# Vario_Kobo_SIDE_V1.net
KiCad netlist of a schematic drawn in EAGLE
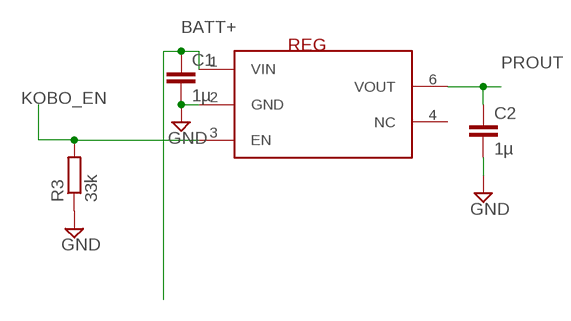
[diagram p0: schematic, sheet 1]
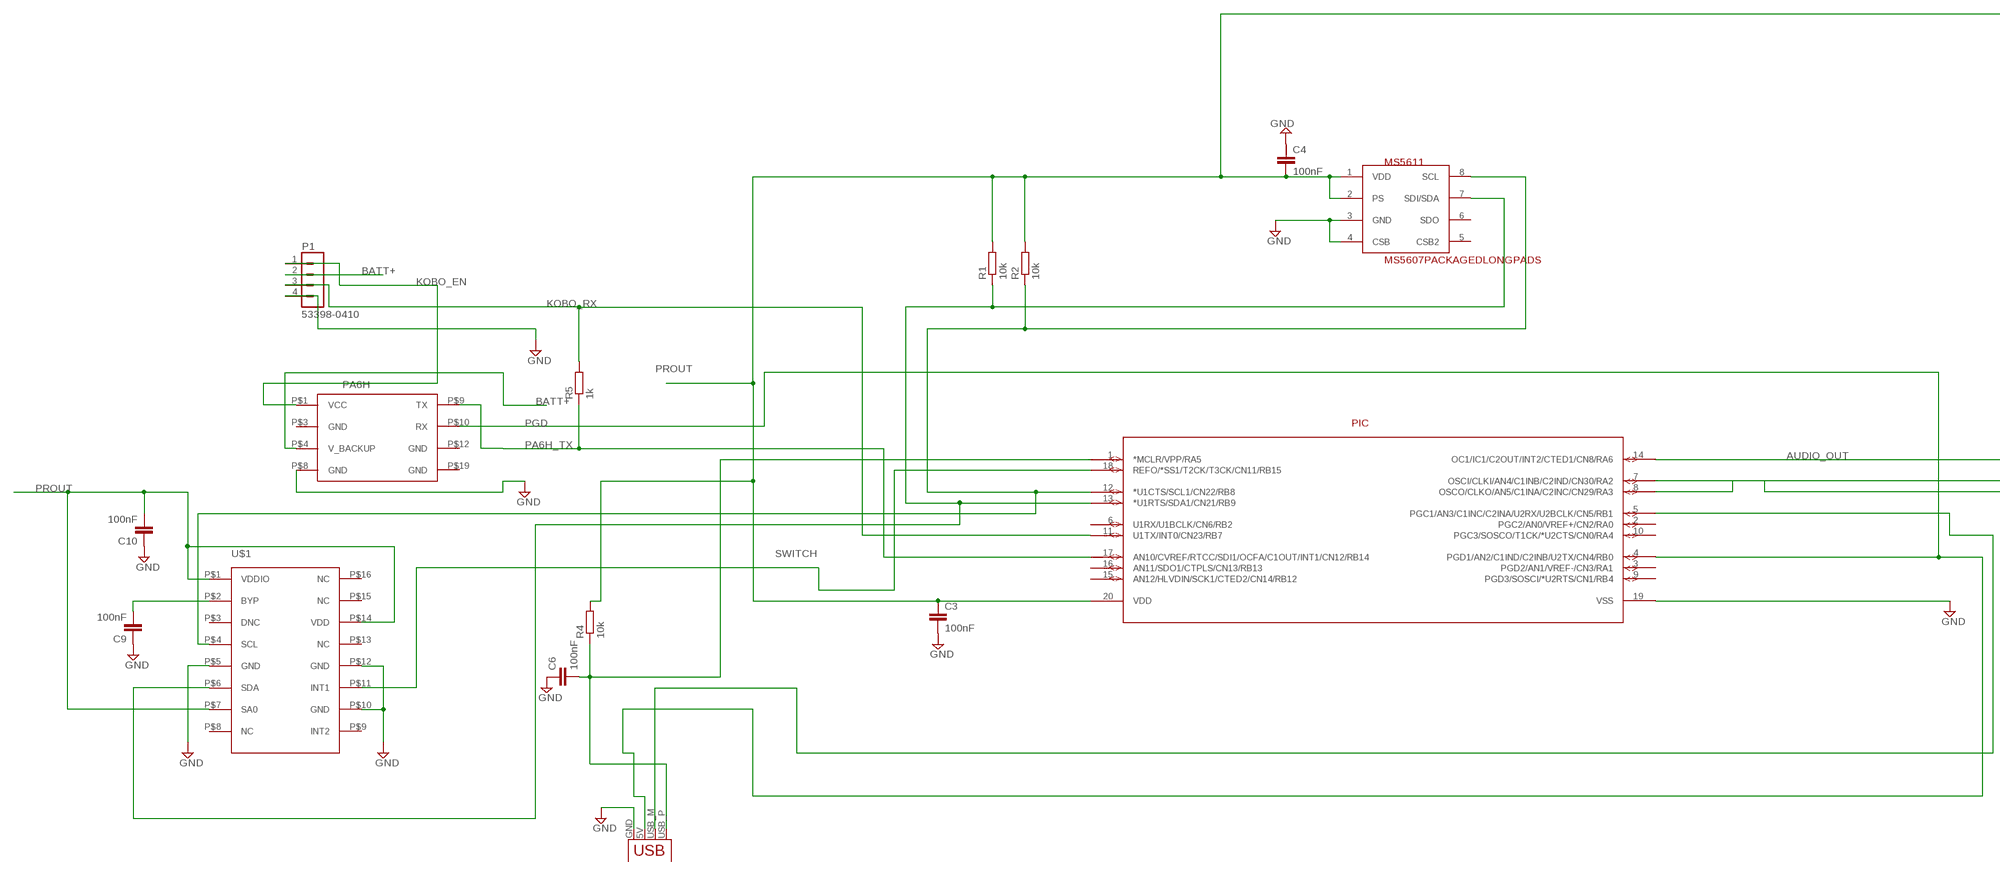
[diagram p1: schematic, sheet 2, part 1 of 2]
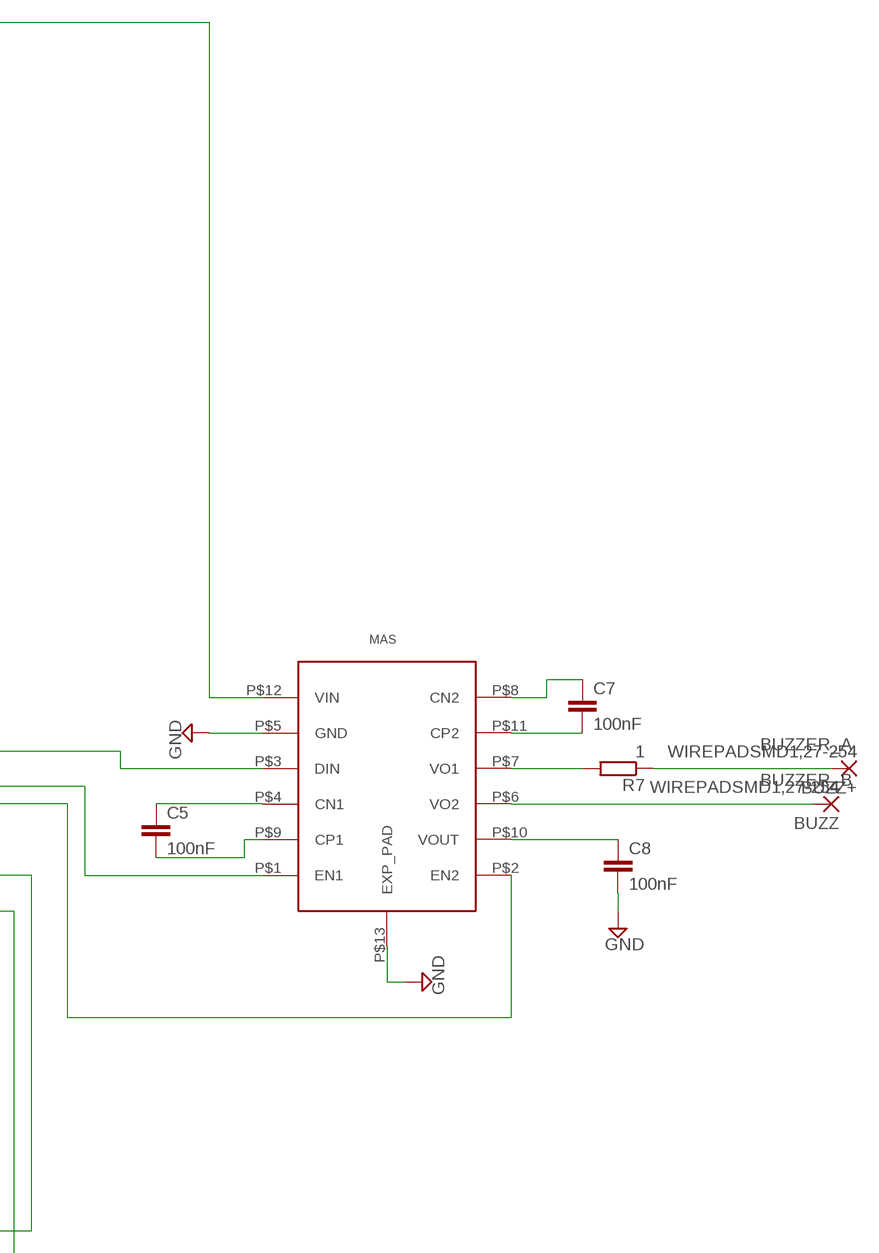
[diagram p2: schematic, sheet 2, part 2 of 2]

(export (version "E")
  (design (tool "Eeschema 10.0.6"))
  (components
    (comp (ref "BUZZ")
      (value "WIREPADSMD1,27-254")
      (footprint "eagle-import:SMD1,27-2,54")
      (libsource (lib "eagle-import") (part "WIREPADSMD1,27-254"))
    )
    (comp (ref "BUZZ+")
      (value "WIREPADSMD1,27-254")
      (footprint "eagle-import:SMD1,27-2,54")
      (libsource (lib "eagle-import") (part "WIREPADSMD1,27-254"))
    )
    (comp (ref "C3")
      (value "100nF")
      (footprint "eagle-import:C0603")
      (libsource (lib "eagle-import") (part "C-EUC0603"))
    )
    (comp (ref "C4")
      (value "100nF")
      (footprint "eagle-import:C0603")
      (libsource (lib "eagle-import") (part "C-EUC0603"))
    )
    (comp (ref "C5")
      (value "100nF")
      (footprint "eagle-import:C0603")
      (libsource (lib "eagle-import") (part "C-EUC0603"))
    )
    (comp (ref "C6")
      (value "100nF")
      (footprint "eagle-import:C0603")
      (libsource (lib "eagle-import") (part "C-EUC0603"))
    )
    (comp (ref "C7")
      (value "100nF")
      (footprint "eagle-import:C0603")
      (libsource (lib "eagle-import") (part "C-EUC0603"))
    )
    (comp (ref "C8")
      (value "100nF")
      (footprint "eagle-import:C0603")
      (libsource (lib "eagle-import") (part "C-EUC0603"))
    )
    (comp (ref "C9")
      (value "100nF")
      (footprint "eagle-import:C0603")
      (libsource (lib "eagle-import") (part "C-EUC0603"))
    )
    (comp (ref "C10")
      (value "100nF")
      (footprint "eagle-import:C0603")
      (libsource (lib "eagle-import") (part "C-EUC0603"))
    )
    (comp (ref "MAS")
      (value "MAS6240")
      (footprint "eagle-import:QFN12_3X3_LONGPADS")
      (libsource (lib "eagle-import") (part "MAS6240"))
    )
    (comp (ref "MS5611")
      (value "MS5607PACKAGEDLONGPADS")
      (footprint "eagle-import:MS5607-02BA03_LONGPADS")
      (libsource (lib "eagle-import") (part "MS5607PACKAGEDLONGPADS"))
    )
    (comp (ref "P1")
      (value "53398-0410")
      (footprint "eagle-import:53398-0410")
      (libsource (lib "eagle-import") (part "53398-0410"))
    )
    (comp (ref "PA6H")
      (value "PA6H")
      (footprint "eagle-import:PA6H_PRINT")
      (libsource (lib "eagle-import") (part "PA6H"))
    )
    (comp (ref "PIC")
      (value "PIC24F16KA101-X_")
      (footprint "eagle-import:SSOP20_MC")
      (libsource (lib "eagle-import") (part "PIC24F16KA101-X_"))
    )
    (comp (ref "R1")
      (value "10k")
      (footprint "eagle-import:R0603")
      (libsource (lib "eagle-import") (part "R-EU_R0603"))
    )
    (comp (ref "R2")
      (value "10k")
      (footprint "eagle-import:R0603")
      (libsource (lib "eagle-import") (part "R-EU_R0603"))
    )
    (comp (ref "R4")
      (value "10k")
      (footprint "eagle-import:R0603")
      (libsource (lib "eagle-import") (part "R-EU_R0603"))
    )
    (comp (ref "R5")
      (value "1k")
      (footprint "eagle-import:R0603")
      (libsource (lib "eagle-import") (part "R-EU_R0603"))
    )
    (comp (ref "R7")
      (value "1")
      (footprint "eagle-import:R0603")
      (libsource (lib "eagle-import") (part "R-EU_R0603"))
    )
    (comp (ref "U$1")
      (value "MMA8452LONGPADS")
      (footprint "eagle-import:MMA845X_LONG_PADS")
      (libsource (lib "eagle-import") (part "MMA8452LONGPADS"))
    )
    (comp (ref "X1")
      (value "USBPCB")
      (footprint "eagle-import:USB-A-PCB")
      (libsource (lib "eagle-import") (part "USBPCB"))
    )
    (comp (ref "C1")
      (value "1µ")
      (footprint "eagle-import:C0603")
      (libsource (lib "eagle-import") (part "C-EUC0603"))
    )
    (comp (ref "C2")
      (value "1µ")
      (footprint "eagle-import:C0603")
      (libsource (lib "eagle-import") (part "C-EUC0603"))
    )
    (comp (ref "R3")
      (value "33k")
      (footprint "eagle-import:R0603")
      (libsource (lib "eagle-import") (part "R-EU_R0603"))
    )
    (comp (ref "REG")
      (value "ADP160/161/162/163")
      (footprint "eagle-import:TSOT23-6_DDC")
      (libsource (lib "eagle-import") (part "ADP160/161/162/163"))
    )
  )
  (nets
    (net (code "1") (name "AUDIO_OUT") (class "Default")
      (node (ref "MAS") (pin "P$3") (pinfunction "DIN_P$3") (pintype "bidirectional"))
      (node (ref "PIC") (pin "14") (pinfunction "OC1/IC1/C2OUT/INT2/CTED1/CN8/RA6_14") (pintype "passive"))
    )
    (net (code "2") (name "BATT+") (class "Default")
      (node (ref "C1") (pin "1") (pinfunction "1_1") (pintype "passive"))
      (node (ref "P1") (pin "2") (pinfunction "2_2") (pintype "passive"))
      (node (ref "PA6H") (pin "P$4") (pinfunction "V_BACKUP_P$4") (pintype "bidirectional"))
      (node (ref "REG") (pin "1") (pinfunction "VIN_1") (pintype "tri_state"))
    )
    (net (code "3") (name "BUZZER_A") (class "Default")
      (node (ref "BUZZ+") (pin "1") (pinfunction "P_1") (pintype "passive"))
      (node (ref "R7") (pin "1") (pinfunction "1_1") (pintype "passive"))
    )
    (net (code "4") (name "BUZZER_B") (class "Default")
      (node (ref "BUZZ") (pin "1") (pinfunction "P_1") (pintype "passive"))
      (node (ref "MAS") (pin "P$6") (pinfunction "VO2_P$6") (pintype "bidirectional"))
    )
    (net (code "5") (name "GND") (class "Default")
      (node (ref "C1") (pin "2") (pinfunction "2_2") (pintype "passive"))
      (node (ref "C10") (pin "1") (pinfunction "1_1") (pintype "passive"))
      (node (ref "C2") (pin "2") (pinfunction "2_2") (pintype "passive"))
      (node (ref "C3") (pin "2") (pinfunction "2_2") (pintype "passive"))
      (node (ref "C4") (pin "1") (pinfunction "1_1") (pintype "passive"))
      (node (ref "C6") (pin "1") (pinfunction "1_1") (pintype "passive"))
      (node (ref "C8") (pin "2") (pinfunction "2_2") (pintype "passive"))
      (node (ref "C9") (pin "1") (pinfunction "1_1") (pintype "passive"))
      (node (ref "MAS") (pin "P$13") (pinfunction "EXP_PAD_P$13") (pintype "bidirectional"))
      (node (ref "MAS") (pin "P$5") (pinfunction "GND_P$5") (pintype "bidirectional"))
      (node (ref "MS5611") (pin "3") (pinfunction "GND_3") (pintype "power_in"))
      (node (ref "MS5611") (pin "4") (pinfunction "CSB_4") (pintype "input"))
      (node (ref "P1") (pin "4") (pinfunction "4_4") (pintype "passive"))
      (node (ref "PA6H") (pin "P$8") (pinfunction "GND_P$8") (pintype "bidirectional"))
      (node (ref "PIC") (pin "19") (pinfunction "VSS_19") (pintype "passive"))
      (node (ref "R3") (pin "1") (pinfunction "1_1") (pintype "passive"))
      (node (ref "REG") (pin "2") (pinfunction "GND_2") (pintype "power_in"))
      (node (ref "U$1") (pin "P$10") (pinfunction "GND_P$10") (pintype "bidirectional"))
      (node (ref "U$1") (pin "P$12") (pinfunction "GND_P$12") (pintype "bidirectional"))
      (node (ref "U$1") (pin "P$5") (pinfunction "GND_P$5") (pintype "bidirectional"))
      (node (ref "X1") (pin "GND") (pinfunction "GND_GND") (pintype "bidirectional"))
    )
    (net (code "6") (name "KOBO_EN") (class "Default")
      (node (ref "P1") (pin "1") (pinfunction "1_1") (pintype "passive"))
      (node (ref "PA6H") (pin "P$1") (pinfunction "VCC_P$1") (pintype "bidirectional"))
      (node (ref "R3") (pin "2") (pinfunction "2_2") (pintype "passive"))
      (node (ref "REG") (pin "3") (pinfunction "EN_3") (pintype "input"))
    )
    (net (code "7") (name "KOBO_RX") (class "Default")
      (node (ref "P1") (pin "3") (pinfunction "3_3") (pintype "passive"))
      (node (ref "PIC") (pin "11") (pinfunction "U1TX/INT0/CN23/RB7_11") (pintype "passive"))
      (node (ref "R5") (pin "2") (pinfunction "2_2") (pintype "passive"))
    )
    (net (code "8") (name "Net-(MAS-CN1)") (class "Default")
      (node (ref "C5") (pin "1") (pinfunction "1_1") (pintype "passive"))
      (node (ref "MAS") (pin "P$4") (pinfunction "CN1_P$4") (pintype "bidirectional"))
    )
    (net (code "9") (name "Net-(MAS-CN2)") (class "Default")
      (node (ref "C7") (pin "1") (pinfunction "1_1") (pintype "passive"))
      (node (ref "MAS") (pin "P$8") (pinfunction "CN2_P$8") (pintype "bidirectional"))
    )
    (net (code "10") (name "Net-(MAS-CP1)") (class "Default")
      (node (ref "C5") (pin "2") (pinfunction "2_2") (pintype "passive"))
      (node (ref "MAS") (pin "P$9") (pinfunction "CP1_P$9") (pintype "bidirectional"))
    )
    (net (code "11") (name "Net-(MAS-CP2)") (class "Default")
      (node (ref "C7") (pin "2") (pinfunction "2_2") (pintype "passive"))
      (node (ref "MAS") (pin "P$11") (pinfunction "CP2_P$11") (pintype "bidirectional"))
    )
    (net (code "12") (name "Net-(MAS-EN1)") (class "Default")
      (node (ref "MAS") (pin "P$1") (pinfunction "EN1_P$1") (pintype "bidirectional"))
      (node (ref "PIC") (pin "8") (pinfunction "OSCO/CLKO/AN5/C1INA/C2INC/CN29/RA3_8") (pintype "passive"))
    )
    (net (code "13") (name "Net-(MAS-EN2)") (class "Default")
      (node (ref "MAS") (pin "P$2") (pinfunction "EN2_P$2") (pintype "bidirectional"))
      (node (ref "PIC") (pin "7") (pinfunction "OSCI/CLKI/AN4/C1INB/C2IND/CN30/RA2_7") (pintype "passive"))
    )
    (net (code "14") (name "Net-(MAS-VO1)") (class "Default")
      (node (ref "MAS") (pin "P$7") (pinfunction "VO1_P$7") (pintype "bidirectional"))
      (node (ref "R7") (pin "2") (pinfunction "2_2") (pintype "passive"))
    )
    (net (code "15") (name "Net-(MAS-VOUT)") (class "Default")
      (node (ref "C8") (pin "1") (pinfunction "1_1") (pintype "passive"))
      (node (ref "MAS") (pin "P$10") (pinfunction "VOUT_P$10") (pintype "bidirectional"))
    )
    (net (code "16") (name "Net-(MS5611-SCL)") (class "Default")
      (node (ref "MS5611") (pin "8") (pinfunction "SCL_8") (pintype "input"))
      (node (ref "PIC") (pin "12") (pinfunction "*U1CTS/SCL1/CN22/RB8_12") (pintype "passive"))
      (node (ref "R2") (pin "1") (pinfunction "1_1") (pintype "passive"))
      (node (ref "U$1") (pin "P$4") (pinfunction "SCL_P$4") (pintype "bidirectional"))
    )
    (net (code "17") (name "Net-(MS5611-SDI{slash}SDA)") (class "Default")
      (node (ref "MS5611") (pin "7") (pinfunction "SDI/SDA_7") (pintype "bidirectional"))
      (node (ref "PIC") (pin "13") (pinfunction "*U1RTS/SDA1/CN21/RB9_13") (pintype "passive"))
      (node (ref "R1") (pin "1") (pinfunction "1_1") (pintype "passive"))
      (node (ref "U$1") (pin "P$6") (pinfunction "SDA_P$6") (pintype "bidirectional"))
    )
    (net (code "18") (name "Net-(PIC-*MCLR{slash}VPP{slash}RA5)") (class "Default")
      (node (ref "C6") (pin "2") (pinfunction "2_2") (pintype "passive"))
      (node (ref "PIC") (pin "1") (pinfunction "*MCLR/VPP/RA5_1") (pintype "passive"))
      (node (ref "R4") (pin "1") (pinfunction "1_1") (pintype "passive"))
      (node (ref "X1") (pin "USB_P") (pinfunction "D+_USB_P") (pintype "bidirectional"))
    )
    (net (code "19") (name "Net-(PIC-PGC1{slash}AN3{slash}C1INC{slash}C2INA{slash}U2RX{slash}U2BCLK{slash}CN5{slash}RB1)") (class "Default")
      (node (ref "PIC") (pin "5") (pinfunction "PGC1/AN3/C1INC/C2INA/U2RX/U2BCLK/CN5/RB1_5") (pintype "passive"))
      (node (ref "X1") (pin "USB_M") (pinfunction "D-_USB_M") (pintype "bidirectional"))
    )
    (net (code "20") (name "Net-(U$1-BYP)") (class "Default")
      (node (ref "C9") (pin "2") (pinfunction "2_2") (pintype "passive"))
      (node (ref "U$1") (pin "P$2") (pinfunction "BYP_P$2") (pintype "bidirectional"))
    )
    (net (code "21") (name "PA6H_TX") (class "Default")
      (node (ref "PA6H") (pin "P$9") (pinfunction "TX_P$9") (pintype "bidirectional"))
      (node (ref "PIC") (pin "17") (pinfunction "AN10/CVREF/RTCC/SDI1/OCFA/C1OUT/INT1/CN12/RB14_17") (pintype "passive"))
      (node (ref "R5") (pin "1") (pinfunction "1_1") (pintype "passive"))
    )
    (net (code "22") (name "PGD") (class "Default")
      (node (ref "PA6H") (pin "P$10") (pinfunction "RX_P$10") (pintype "bidirectional"))
      (node (ref "PIC") (pin "4") (pinfunction "PGD1/AN2/C1IND/C2INB/U2TX/CN4/RB0_4") (pintype "passive"))
      (node (ref "X1") (pin "5V") (pinfunction "VBUS_5V") (pintype "bidirectional"))
    )
    (net (code "23") (name "PROUT") (class "Default")
      (node (ref "C10") (pin "2") (pinfunction "2_2") (pintype "passive"))
      (node (ref "C2") (pin "1") (pinfunction "1_1") (pintype "passive"))
      (node (ref "C3") (pin "1") (pinfunction "1_1") (pintype "passive"))
      (node (ref "C4") (pin "2") (pinfunction "2_2") (pintype "passive"))
      (node (ref "MAS") (pin "P$12") (pinfunction "VIN_P$12") (pintype "bidirectional"))
      (node (ref "MS5611") (pin "1") (pinfunction "VDD_1") (pintype "power_in"))
      (node (ref "MS5611") (pin "2") (pinfunction "PS_2") (pintype "input"))
      (node (ref "PIC") (pin "20") (pinfunction "VDD_20") (pintype "passive"))
      (node (ref "R1") (pin "2") (pinfunction "2_2") (pintype "passive"))
      (node (ref "R2") (pin "2") (pinfunction "2_2") (pintype "passive"))
      (node (ref "R4") (pin "2") (pinfunction "2_2") (pintype "passive"))
      (node (ref "REG") (pin "6") (pinfunction "VOUT_6") (pintype "bidirectional"))
      (node (ref "U$1") (pin "P$1") (pinfunction "VDDIO_P$1") (pintype "bidirectional"))
      (node (ref "U$1") (pin "P$14") (pinfunction "VDD_P$14") (pintype "bidirectional"))
      (node (ref "U$1") (pin "P$7") (pinfunction "SA0_P$7") (pintype "bidirectional"))
    )
    (net (code "24") (name "SWITCH") (class "Default")
      (node (ref "PIC") (pin "18") (pinfunction "REFO/*SS1/T2CK/T3CK/CN11/RB15_18") (pintype "passive"))
      (node (ref "U$1") (pin "P$11") (pinfunction "INT1_P$11") (pintype "bidirectional"))
    )
    (net (code "25") (name "unconnected-(MS5611-CSB2-Pad5)") (class "Default")
      (node (ref "MS5611") (pin "5") (pinfunction "CSB2_5") (pintype "input"))
    )
    (net (code "26") (name "unconnected-(MS5611-SDO-Pad6)") (class "Default")
      (node (ref "MS5611") (pin "6") (pinfunction "SDO_6") (pintype "output"))
    )
    (net (code "27") (name "unconnected-(PA6H-GND-PadP$3)") (class "Default")
      (node (ref "PA6H") (pin "P$3") (pinfunction "GND_P$3") (pintype "bidirectional"))
    )
    (net (code "28") (name "unconnected-(PA6H-GND-PadP$12)") (class "Default")
      (node (ref "PA6H") (pin "P$12") (pinfunction "GND_P$12") (pintype "bidirectional"))
    )
    (net (code "29") (name "unconnected-(PA6H-GND-PadP$19)") (class "Default")
      (node (ref "PA6H") (pin "P$19") (pinfunction "GND_P$19") (pintype "bidirectional"))
    )
    (net (code "30") (name "unconnected-(PIC-AN11{slash}SDO1{slash}CTPLS{slash}CN13{slash}RB13-Pad16)") (class "Default")
      (node (ref "PIC") (pin "16") (pinfunction "AN11/SDO1/CTPLS/CN13/RB13_16") (pintype "passive"))
    )
    (net (code "31") (name "unconnected-(PIC-AN12{slash}HLVDIN{slash}SCK1{slash}CTED2{slash}CN14{slash}RB12-Pad15)") (class "Default")
      (node (ref "PIC") (pin "15") (pinfunction "AN12/HLVDIN/SCK1/CTED2/CN14/RB12_15") (pintype "passive"))
    )
    (net (code "32") (name "unconnected-(PIC-PGC2{slash}AN0{slash}VREF+{slash}CN2{slash}RA0-Pad2)") (class "Default")
      (node (ref "PIC") (pin "2") (pinfunction "PGC2/AN0/VREF+/CN2/RA0_2") (pintype "passive"))
    )
    (net (code "33") (name "unconnected-(PIC-PGC3{slash}SOSCO{slash}T1CK{slash}*U2CTS{slash}CN0{slash}RA4-Pad10)") (class "Default")
      (node (ref "PIC") (pin "10") (pinfunction "PGC3/SOSCO/T1CK/*U2CTS/CN0/RA4_10") (pintype "passive"))
    )
    (net (code "34") (name "unconnected-(PIC-PGD2{slash}AN1{slash}VREF-{slash}CN3{slash}RA1-Pad3)") (class "Default")
      (node (ref "PIC") (pin "3") (pinfunction "PGD2/AN1/VREF-/CN3/RA1_3") (pintype "passive"))
    )
    (net (code "35") (name "unconnected-(PIC-PGD3{slash}SOSCI{slash}*U2RTS{slash}CN1{slash}RB4-Pad9)") (class "Default")
      (node (ref "PIC") (pin "9") (pinfunction "PGD3/SOSCI/*U2RTS/CN1/RB4_9") (pintype "passive"))
    )
    (net (code "36") (name "unconnected-(PIC-U1RX{slash}U1BCLK{slash}CN6{slash}RB2-Pad6)") (class "Default")
      (node (ref "PIC") (pin "6") (pinfunction "U1RX/U1BCLK/CN6/RB2_6") (pintype "passive"))
    )
    (net (code "37") (name "unconnected-(REG-NC-Pad4)") (class "Default")
      (node (ref "REG") (pin "4") (pinfunction "NC_4") (pintype "no_connect"))
    )
    (net (code "38") (name "unconnected-(U$1-DNC-PadP$3)") (class "Default")
      (node (ref "U$1") (pin "P$3") (pinfunction "DNC_P$3") (pintype "bidirectional"))
    )
    (net (code "39") (name "unconnected-(U$1-INT2-PadP$9)") (class "Default")
      (node (ref "U$1") (pin "P$9") (pinfunction "INT2_P$9") (pintype "bidirectional"))
    )
    (net (code "40") (name "unconnected-(U$1-NC-PadP$8)") (class "Default")
      (node (ref "U$1") (pin "P$8") (pinfunction "NC_P$8") (pintype "bidirectional"))
    )
    (net (code "41") (name "unconnected-(U$1-NC-PadP$13)") (class "Default")
      (node (ref "U$1") (pin "P$13") (pinfunction "NC_P$13") (pintype "bidirectional"))
    )
    (net (code "42") (name "unconnected-(U$1-NC-PadP$15)") (class "Default")
      (node (ref "U$1") (pin "P$15") (pinfunction "NC_P$15") (pintype "bidirectional"))
    )
    (net (code "43") (name "unconnected-(U$1-NC-PadP$16)") (class "Default")
      (node (ref "U$1") (pin "P$16") (pinfunction "NC_P$16") (pintype "bidirectional"))
    )
  )
)
